# MB_RELAY.net
KiCad netlist of a schematic drawn in Altium Designer
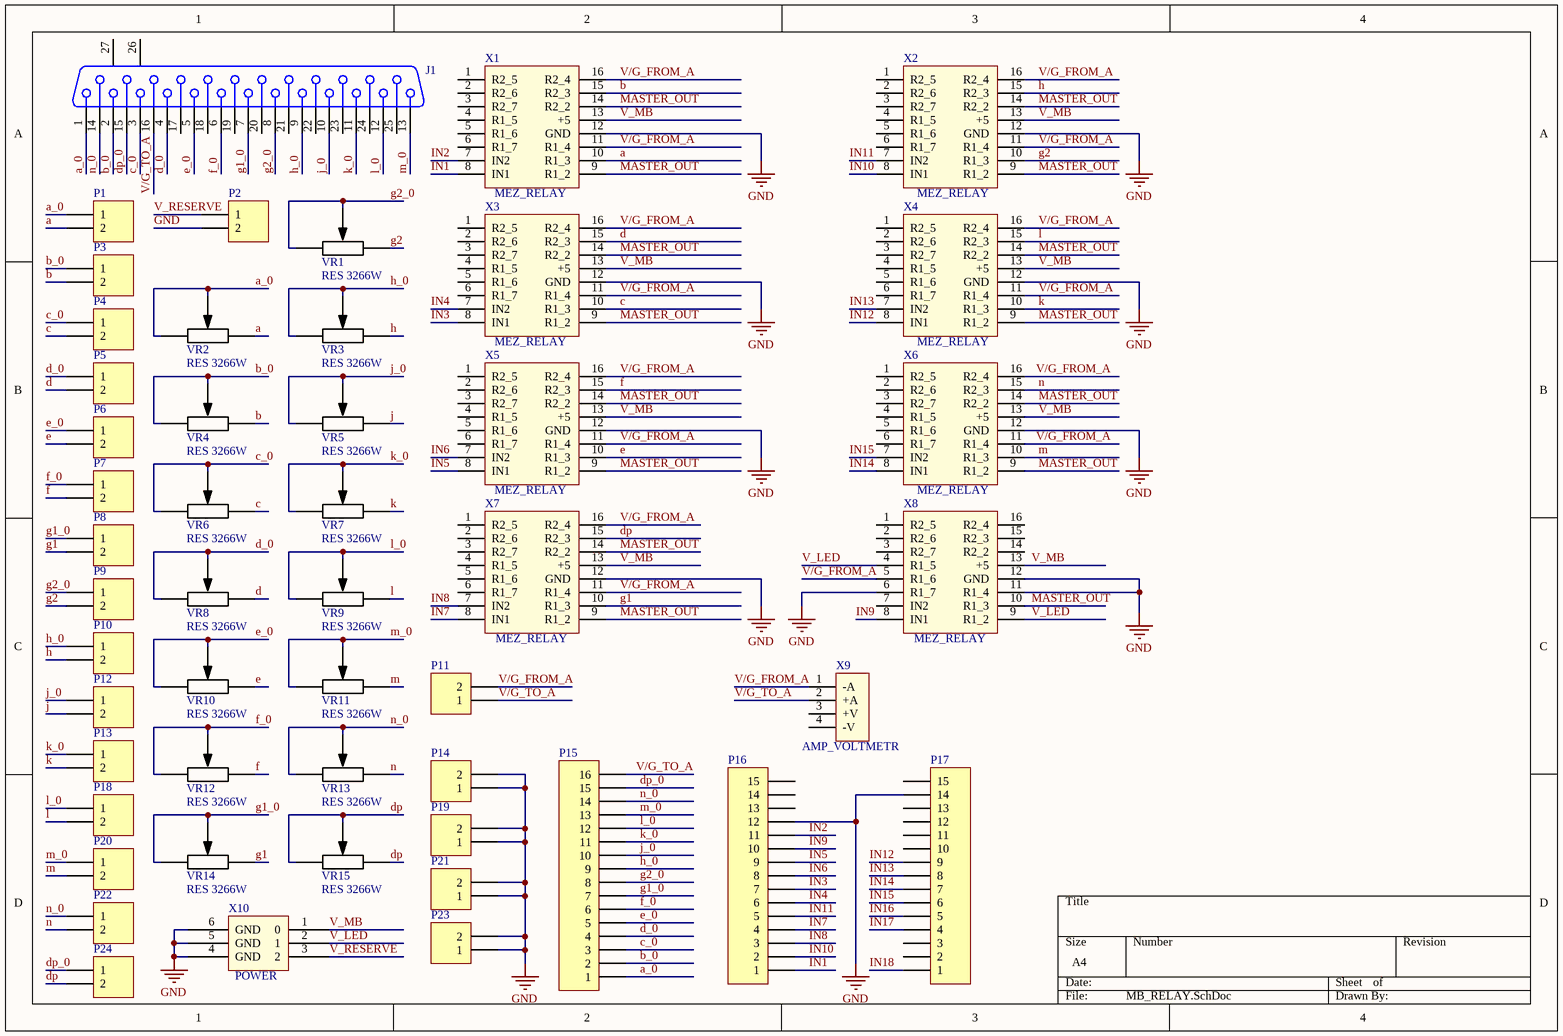
[diagram p0: MB_RELAY.SchDoc]

(export (version "E")
  (design (tool "Eeschema 10.0.6"))
  (components
    (comp (ref "J1")
      (value "D Connector 25")
      (footprint "DSUB1.385-2H25A")
      (description "Receptacle Assembly, 25 Position, Right Angle")
      (fields (field (name "PUBLISHER") "Altium Limited"))
      (libsource (lib "Miscellaneous Connectors") (part "D Connector 25"))
    )
    (comp (ref "P1")
      (value "Header 2")
      (footprint "HDR1X2")
      (description "Header, 2-Pin")
      (fields (field (name "PUBLISHER") "Altium Limited"))
      (libsource (lib "Miscellaneous Connectors") (part "Header 2"))
    )
    (comp (ref "P2")
      (value "Header 2")
      (footprint "HDR1X2")
      (description "Header, 2-Pin")
      (fields (field (name "PUBLISHER") "Altium Limited"))
      (libsource (lib "Miscellaneous Connectors") (part "Header 2"))
    )
    (comp (ref "P3")
      (value "Header 2")
      (footprint "HDR1X2")
      (description "Header, 2-Pin")
      (fields (field (name "PUBLISHER") "Altium Limited"))
      (libsource (lib "Miscellaneous Connectors") (part "Header 2"))
    )
    (comp (ref "P4")
      (value "Header 2")
      (footprint "HDR1X2")
      (description "Header, 2-Pin")
      (fields (field (name "PUBLISHER") "Altium Limited"))
      (libsource (lib "Miscellaneous Connectors") (part "Header 2"))
    )
    (comp (ref "P5")
      (value "Header 2")
      (footprint "HDR1X2")
      (description "Header, 2-Pin")
      (fields (field (name "PUBLISHER") "Altium Limited"))
      (libsource (lib "Miscellaneous Connectors") (part "Header 2"))
    )
    (comp (ref "P6")
      (value "GND")
      (footprint "HDR1X2")
      (description "Header, 2-Pin")
      (fields (field (name "PUBLISHER") "Altium Limited"))
      (libsource (lib "Miscellaneous Connectors") (part "Header 2"))
    )
    (comp (ref "P7")
      (value "GND")
      (footprint "HDR1X2")
      (description "Header, 2-Pin")
      (fields (field (name "PUBLISHER") "Altium Limited"))
      (libsource (lib "Miscellaneous Connectors") (part "Header 2"))
    )
    (comp (ref "P8")
      (value "GND")
      (footprint "HDR1X2")
      (description "Header, 2-Pin")
      (fields (field (name "PUBLISHER") "Altium Limited"))
      (libsource (lib "Miscellaneous Connectors") (part "Header 2"))
    )
    (comp (ref "P9")
      (value "GND")
      (footprint "HDR1X2")
      (description "Header, 2-Pin")
      (fields (field (name "PUBLISHER") "Altium Limited"))
      (libsource (lib "Miscellaneous Connectors") (part "Header 2"))
    )
    (comp (ref "P10")
      (value "Header 2")
      (footprint "HDR1X2")
      (description "Header, 2-Pin")
      (fields (field (name "PUBLISHER") "Altium Limited"))
      (libsource (lib "Miscellaneous Connectors") (part "Header 2"))
    )
    (comp (ref "P11")
      (value "Header 2")
      (footprint "HDR1X2")
      (description "Header, 2-Pin")
      (fields (field (name "PUBLISHER") "Altium Limited"))
      (libsource (lib "") (part "Header 2_1"))
    )
    (comp (ref "P12")
      (value "Header 2")
      (footprint "HDR1X2")
      (description "Header, 2-Pin")
      (fields (field (name "PUBLISHER") "Altium Limited"))
      (libsource (lib "Miscellaneous Connectors") (part "Header 2"))
    )
    (comp (ref "P13")
      (value "GND")
      (footprint "HDR1X2")
      (description "Header, 2-Pin")
      (fields (field (name "PUBLISHER") "Altium Limited"))
      (libsource (lib "Miscellaneous Connectors") (part "Header 2"))
    )
    (comp (ref "P14")
      (value "GND")
      (footprint "HDR1X2")
      (description "Header, 2-Pin")
      (fields (field (name "PUBLISHER") "Altium Limited"))
      (libsource (lib "") (part "Header 2_1"))
    )
    (comp (ref "P15")
      (value "Header 16")
      (footprint "HDR1X16")
      (description "Header, 16-Pin")
      (fields (field (name "PUBLISHER") "Altium Limited"))
      (libsource (lib "Miscellaneous Connectors") (part "Header 16"))
    )
    (comp (ref "P16")
      (value "Header 15")
      (footprint "HDR1X15")
      (description "Header, 15-Pin")
      (fields (field (name "PUBLISHER") "Altium Limited"))
      (libsource (lib "") (part "Header 15_1"))
    )
    (comp (ref "P17")
      (value "Header 15")
      (footprint "HDR1X15")
      (description "Header, 15-Pin")
      (fields (field (name "PUBLISHER") "Altium Limited"))
      (libsource (lib "Miscellaneous Connectors") (part "Header 15"))
    )
    (comp (ref "P18")
      (value "GND")
      (footprint "HDR1X2")
      (description "Header, 2-Pin")
      (fields (field (name "PUBLISHER") "Altium Limited"))
      (libsource (lib "Miscellaneous Connectors") (part "Header 2"))
    )
    (comp (ref "P19")
      (value "GND")
      (footprint "HDR1X2")
      (description "Header, 2-Pin")
      (fields (field (name "PUBLISHER") "Altium Limited"))
      (libsource (lib "") (part "Header 2_1"))
    )
    (comp (ref "P20")
      (value "GND")
      (footprint "HDR1X2")
      (description "Header, 2-Pin")
      (fields (field (name "PUBLISHER") "Altium Limited"))
      (libsource (lib "Miscellaneous Connectors") (part "Header 2"))
    )
    (comp (ref "P21")
      (value "GND")
      (footprint "HDR1X2")
      (description "Header, 2-Pin")
      (fields (field (name "PUBLISHER") "Altium Limited"))
      (libsource (lib "") (part "Header 2_1"))
    )
    (comp (ref "P22")
      (value "GND")
      (footprint "HDR1X2")
      (description "Header, 2-Pin")
      (fields (field (name "PUBLISHER") "Altium Limited"))
      (libsource (lib "Miscellaneous Connectors") (part "Header 2"))
    )
    (comp (ref "P23")
      (value "GND")
      (footprint "HDR1X2")
      (description "Header, 2-Pin")
      (fields (field (name "PUBLISHER") "Altium Limited"))
      (libsource (lib "") (part "Header 2_1"))
    )
    (comp (ref "P24")
      (value "GND")
      (footprint "HDR1X2")
      (description "Header, 2-Pin")
      (fields (field (name "PUBLISHER") "Altium Limited"))
      (libsource (lib "Miscellaneous Connectors") (part "Header 2"))
    )
    (comp (ref "VR1")
      (value "RES 3266W")
      (footprint "aab_Passive:RES 3266W")
      (libsource (lib "aab_Schlib") (part "RES 3266W"))
    )
    (comp (ref "VR2")
      (value "RES 3266W")
      (footprint "aab_Passive:RES 3266W")
      (libsource (lib "aab_Schlib") (part "RES 3266W"))
    )
    (comp (ref "VR3")
      (value "RES 3266W")
      (footprint "aab_Passive:RES 3266W")
      (libsource (lib "aab_Schlib") (part "RES 3266W"))
    )
    (comp (ref "VR4")
      (value "RES 3266W")
      (footprint "aab_Passive:RES 3266W")
      (libsource (lib "aab_Schlib") (part "RES 3266W"))
    )
    (comp (ref "VR5")
      (value "RES 3266W")
      (footprint "aab_Passive:RES 3266W")
      (libsource (lib "aab_Schlib") (part "RES 3266W"))
    )
    (comp (ref "VR6")
      (value "RES 3266W")
      (footprint "aab_Passive:RES 3266W")
      (libsource (lib "aab_Schlib") (part "RES 3266W"))
    )
    (comp (ref "VR7")
      (value "RES 3266W")
      (footprint "aab_Passive:RES 3266W")
      (libsource (lib "aab_Schlib") (part "RES 3266W"))
    )
    (comp (ref "VR8")
      (value "RES 3266W")
      (footprint "aab_Passive:RES 3266W")
      (libsource (lib "aab_Schlib") (part "RES 3266W"))
    )
    (comp (ref "VR9")
      (value "RES 3266W")
      (footprint "aab_Passive:RES 3266W")
      (libsource (lib "aab_Schlib") (part "RES 3266W"))
    )
    (comp (ref "VR10")
      (value "RES 3266W")
      (footprint "aab_Passive:RES 3266W")
      (libsource (lib "aab_Schlib") (part "RES 3266W"))
    )
    (comp (ref "VR11")
      (value "RES 3266W")
      (footprint "aab_Passive:RES 3266W")
      (libsource (lib "aab_Schlib") (part "RES 3266W"))
    )
    (comp (ref "VR12")
      (value "RES 3266W")
      (footprint "aab_Passive:RES 3266W")
      (libsource (lib "aab_Schlib") (part "RES 3266W"))
    )
    (comp (ref "VR13")
      (value "RES 3266W")
      (footprint "aab_Passive:RES 3266W")
      (libsource (lib "aab_Schlib") (part "RES 3266W"))
    )
    (comp (ref "VR14")
      (value "RES 3266W")
      (footprint "aab_Passive:RES 3266W")
      (libsource (lib "aab_Schlib") (part "RES 3266W"))
    )
    (comp (ref "VR15")
      (value "RES 3266W")
      (footprint "aab_Passive:RES 3266W")
      (libsource (lib "aab_Schlib") (part "RES 3266W"))
    )
    (comp (ref "X1")
      (value "MEZ_RELAY")
      (footprint "MEZ_RELAY")
      (libsource (lib "msp_SchLib") (part "MEZ_RELAY"))
    )
    (comp (ref "X2")
      (value "MEZ_RELAY")
      (footprint "MEZ_RELAY")
      (libsource (lib "msp_SchLib") (part "MEZ_RELAY"))
    )
    (comp (ref "X3")
      (value "MEZ_RELAY")
      (footprint "MEZ_RELAY")
      (libsource (lib "msp_SchLib") (part "MEZ_RELAY"))
    )
    (comp (ref "X4")
      (value "MEZ_RELAY")
      (footprint "MEZ_RELAY")
      (libsource (lib "msp_SchLib") (part "MEZ_RELAY"))
    )
    (comp (ref "X5")
      (value "MEZ_RELAY")
      (footprint "MEZ_RELAY")
      (libsource (lib "msp_SchLib") (part "MEZ_RELAY"))
    )
    (comp (ref "X6")
      (value "MEZ_RELAY")
      (footprint "MEZ_RELAY")
      (libsource (lib "msp_SchLib") (part "MEZ_RELAY"))
    )
    (comp (ref "X7")
      (value "MEZ_RELAY")
      (footprint "MEZ_RELAY")
      (libsource (lib "msp_SchLib") (part "MEZ_RELAY"))
    )
    (comp (ref "X8")
      (value "MEZ_RELAY")
      (footprint "MEZ_RELAY")
      (libsource (lib "msp_SchLib") (part "MEZ_RELAY"))
    )
    (comp (ref "X9")
      (value "AMP_VOLTMETR")
      (footprint "vpl_Passive:AMP_VOLTMETER")
      (libsource (lib "msp_SchLib") (part "AMP_VOLTMETR"))
    )
    (comp (ref "X10")
      (value "POWER")
      (footprint "vpl_Passive:POWER")
      (libsource (lib "msp_SchLib") (part "POWER"))
    )
  )
  (nets
    (net (code "1") (name "/IN1") (class "Default")
      (node (ref "P16") (pin "1") (pinfunction "1_1") (pintype "passive"))
      (node (ref "X1") (pin "8") (pinfunction "IN1_8") (pintype "passive"))
    )
    (net (code "2") (name "/IN2") (class "Default")
      (node (ref "P16") (pin "11") (pinfunction "11_11") (pintype "passive"))
      (node (ref "X1") (pin "7") (pinfunction "IN2_7") (pintype "passive"))
    )
    (net (code "3") (name "/IN3") (class "Default")
      (node (ref "P16") (pin "7") (pinfunction "7_7") (pintype "passive"))
      (node (ref "X3") (pin "8") (pinfunction "IN1_8") (pintype "passive"))
    )
    (net (code "4") (name "/IN4") (class "Default")
      (node (ref "P16") (pin "6") (pinfunction "6_6") (pintype "passive"))
      (node (ref "X3") (pin "7") (pinfunction "IN2_7") (pintype "passive"))
    )
    (net (code "5") (name "/IN5") (class "Default")
      (node (ref "P16") (pin "9") (pinfunction "9_9") (pintype "passive"))
      (node (ref "X5") (pin "8") (pinfunction "IN1_8") (pintype "passive"))
    )
    (net (code "6") (name "/IN6") (class "Default")
      (node (ref "P16") (pin "8") (pinfunction "8_8") (pintype "passive"))
      (node (ref "X5") (pin "7") (pinfunction "IN2_7") (pintype "passive"))
    )
    (net (code "7") (name "/IN7") (class "Default")
      (node (ref "P16") (pin "4") (pinfunction "4_4") (pintype "passive"))
      (node (ref "X7") (pin "8") (pinfunction "IN1_8") (pintype "passive"))
    )
    (net (code "8") (name "/IN8") (class "Default")
      (node (ref "P16") (pin "3") (pinfunction "3_3") (pintype "passive"))
      (node (ref "X7") (pin "7") (pinfunction "IN2_7") (pintype "passive"))
    )
    (net (code "9") (name "/IN9") (class "Default")
      (node (ref "P16") (pin "10") (pinfunction "10_10") (pintype "passive"))
      (node (ref "X8") (pin "8") (pinfunction "IN1_8") (pintype "passive"))
    )
    (net (code "10") (name "/IN10") (class "Default")
      (node (ref "P16") (pin "2") (pinfunction "2_2") (pintype "passive"))
      (node (ref "X2") (pin "8") (pinfunction "IN1_8") (pintype "passive"))
    )
    (net (code "11") (name "/IN11") (class "Default")
      (node (ref "P16") (pin "5") (pinfunction "5_5") (pintype "passive"))
      (node (ref "X2") (pin "7") (pinfunction "IN2_7") (pintype "passive"))
    )
    (net (code "12") (name "/IN12") (class "Default")
      (node (ref "P17") (pin "9") (pinfunction "9_9") (pintype "passive"))
      (node (ref "X4") (pin "8") (pinfunction "IN1_8") (pintype "passive"))
    )
    (net (code "13") (name "/IN13") (class "Default")
      (node (ref "P17") (pin "8") (pinfunction "8_8") (pintype "passive"))
      (node (ref "X4") (pin "7") (pinfunction "IN2_7") (pintype "passive"))
    )
    (net (code "14") (name "/IN14") (class "Default")
      (node (ref "P17") (pin "7") (pinfunction "7_7") (pintype "passive"))
      (node (ref "X6") (pin "8") (pinfunction "IN1_8") (pintype "passive"))
    )
    (net (code "15") (name "/IN15") (class "Default")
      (node (ref "P17") (pin "6") (pinfunction "6_6") (pintype "passive"))
      (node (ref "X6") (pin "7") (pinfunction "IN2_7") (pintype "passive"))
    )
    (net (code "16") (name "/IN16") (class "Default")
      (node (ref "P17") (pin "5") (pinfunction "5_5") (pintype "passive"))
    )
    (net (code "17") (name "/IN17") (class "Default")
      (node (ref "P17") (pin "4") (pinfunction "4_4") (pintype "passive"))
    )
    (net (code "18") (name "/IN18") (class "Default")
      (node (ref "P17") (pin "1") (pinfunction "1_1") (pintype "passive"))
    )
    (net (code "19") (name "/MASTER_OUT") (class "Default")
      (node (ref "X1") (pin "14") (pinfunction "R2_2_14") (pintype "passive"))
      (node (ref "X1") (pin "9") (pinfunction "R1_2_9") (pintype "passive"))
      (node (ref "X2") (pin "14") (pinfunction "R2_2_14") (pintype "passive"))
      (node (ref "X2") (pin "9") (pinfunction "R1_2_9") (pintype "passive"))
      (node (ref "X3") (pin "14") (pinfunction "R2_2_14") (pintype "passive"))
      (node (ref "X3") (pin "9") (pinfunction "R1_2_9") (pintype "passive"))
      (node (ref "X4") (pin "14") (pinfunction "R2_2_14") (pintype "passive"))
      (node (ref "X4") (pin "9") (pinfunction "R1_2_9") (pintype "passive"))
      (node (ref "X5") (pin "14") (pinfunction "R2_2_14") (pintype "passive"))
      (node (ref "X5") (pin "9") (pinfunction "R1_2_9") (pintype "passive"))
      (node (ref "X6") (pin "14") (pinfunction "R2_2_14") (pintype "passive"))
      (node (ref "X6") (pin "9") (pinfunction "R1_2_9") (pintype "passive"))
      (node (ref "X7") (pin "14") (pinfunction "R2_2_14") (pintype "passive"))
      (node (ref "X7") (pin "9") (pinfunction "R1_2_9") (pintype "passive"))
      (node (ref "X8") (pin "10") (pinfunction "R1_3_10") (pintype "passive"))
    )
    (net (code "20") (name "/V_LED") (class "Default")
      (node (ref "X10") (pin "2") (pinfunction "1_2") (pintype "passive"))
      (node (ref "X8") (pin "4") (pinfunction "R1_5_4") (pintype "passive"))
      (node (ref "X8") (pin "9") (pinfunction "R1_2_9") (pintype "passive"))
    )
    (net (code "21") (name "/V_MB") (class "Default")
      (node (ref "X1") (pin "13") (pinfunction "+5_13") (pintype "passive"))
      (node (ref "X10") (pin "1") (pinfunction "0_1") (pintype "passive"))
      (node (ref "X2") (pin "13") (pinfunction "+5_13") (pintype "passive"))
      (node (ref "X3") (pin "13") (pinfunction "+5_13") (pintype "passive"))
      (node (ref "X4") (pin "13") (pinfunction "+5_13") (pintype "passive"))
      (node (ref "X5") (pin "13") (pinfunction "+5_13") (pintype "passive"))
      (node (ref "X6") (pin "13") (pinfunction "+5_13") (pintype "passive"))
      (node (ref "X7") (pin "13") (pinfunction "+5_13") (pintype "passive"))
      (node (ref "X8") (pin "13") (pinfunction "+5_13") (pintype "passive"))
    )
    (net (code "22") (name "/V_RESERVE") (class "Default")
      (node (ref "P2") (pin "1") (pinfunction "1_1") (pintype "passive"))
      (node (ref "X10") (pin "3") (pinfunction "2_3") (pintype "passive"))
    )
    (net (code "23") (name "/V{slash}G_FROM_A") (class "Default")
      (node (ref "P11") (pin "2") (pinfunction "2_2") (pintype "passive"))
      (node (ref "X1") (pin "11") (pinfunction "R1_4_11") (pintype "passive"))
      (node (ref "X1") (pin "16") (pinfunction "R2_4_16") (pintype "passive"))
      (node (ref "X2") (pin "11") (pinfunction "R1_4_11") (pintype "passive"))
      (node (ref "X2") (pin "16") (pinfunction "R2_4_16") (pintype "passive"))
      (node (ref "X3") (pin "11") (pinfunction "R1_4_11") (pintype "passive"))
      (node (ref "X3") (pin "16") (pinfunction "R2_4_16") (pintype "passive"))
      (node (ref "X4") (pin "11") (pinfunction "R1_4_11") (pintype "passive"))
      (node (ref "X4") (pin "16") (pinfunction "R2_4_16") (pintype "passive"))
      (node (ref "X5") (pin "11") (pinfunction "R1_4_11") (pintype "passive"))
      (node (ref "X5") (pin "16") (pinfunction "R2_4_16") (pintype "passive"))
      (node (ref "X6") (pin "11") (pinfunction "R1_4_11") (pintype "passive"))
      (node (ref "X6") (pin "16") (pinfunction "R2_4_16") (pintype "passive"))
      (node (ref "X7") (pin "11") (pinfunction "R1_4_11") (pintype "passive"))
      (node (ref "X7") (pin "16") (pinfunction "R2_4_16") (pintype "passive"))
      (node (ref "X8") (pin "5") (pinfunction "R1_6_5") (pintype "passive"))
      (node (ref "X9") (pin "1") (pinfunction "-A_1") (pintype "passive"))
    )
    (net (code "24") (name "/V{slash}G_TO_A") (class "Default")
      (node (ref "J1") (pin "16") (pinfunction "16_16") (pintype "passive"))
      (node (ref "P11") (pin "1") (pinfunction "1_1") (pintype "passive"))
      (node (ref "P15") (pin "16") (pinfunction "16_16") (pintype "passive"))
      (node (ref "X9") (pin "2") (pinfunction "+A_2") (pintype "passive"))
    )
    (net (code "25") (name "/a") (class "Default")
      (node (ref "P1") (pin "2") (pinfunction "2_2") (pintype "passive"))
      (node (ref "VR2") (pin "3") (pinfunction "3_3") (pintype "passive"))
      (node (ref "X1") (pin "10") (pinfunction "R1_3_10") (pintype "passive"))
    )
    (net (code "26") (name "/a_0") (class "Default")
      (node (ref "J1") (pin "1") (pinfunction "1_1") (pintype "passive"))
      (node (ref "P1") (pin "1") (pinfunction "1_1") (pintype "passive"))
      (node (ref "P15") (pin "1") (pinfunction "1_1") (pintype "passive"))
      (node (ref "VR2") (pin "1") (pinfunction "1_1") (pintype "passive"))
      (node (ref "VR2") (pin "2") (pinfunction "2_2") (pintype "passive"))
    )
    (net (code "27") (name "/b") (class "Default")
      (node (ref "P3") (pin "2") (pinfunction "2_2") (pintype "passive"))
      (node (ref "VR4") (pin "3") (pinfunction "3_3") (pintype "passive"))
      (node (ref "X1") (pin "15") (pinfunction "R2_3_15") (pintype "passive"))
    )
    (net (code "28") (name "/b_0") (class "Default")
      (node (ref "J1") (pin "2") (pinfunction "2_2") (pintype "passive"))
      (node (ref "P15") (pin "2") (pinfunction "2_2") (pintype "passive"))
      (node (ref "P3") (pin "1") (pinfunction "1_1") (pintype "passive"))
      (node (ref "VR4") (pin "1") (pinfunction "1_1") (pintype "passive"))
      (node (ref "VR4") (pin "2") (pinfunction "2_2") (pintype "passive"))
    )
    (net (code "29") (name "/c") (class "Default")
      (node (ref "P4") (pin "2") (pinfunction "2_2") (pintype "passive"))
      (node (ref "VR6") (pin "3") (pinfunction "3_3") (pintype "passive"))
      (node (ref "X3") (pin "10") (pinfunction "R1_3_10") (pintype "passive"))
    )
    (net (code "30") (name "/c_0") (class "Default")
      (node (ref "J1") (pin "3") (pinfunction "3_3") (pintype "passive"))
      (node (ref "P15") (pin "3") (pinfunction "3_3") (pintype "passive"))
      (node (ref "P4") (pin "1") (pinfunction "1_1") (pintype "passive"))
      (node (ref "VR6") (pin "1") (pinfunction "1_1") (pintype "passive"))
      (node (ref "VR6") (pin "2") (pinfunction "2_2") (pintype "passive"))
    )
    (net (code "31") (name "/d") (class "Default")
      (node (ref "P5") (pin "2") (pinfunction "2_2") (pintype "passive"))
      (node (ref "VR8") (pin "3") (pinfunction "3_3") (pintype "passive"))
      (node (ref "X3") (pin "15") (pinfunction "R2_3_15") (pintype "passive"))
    )
    (net (code "32") (name "/d_0") (class "Default")
      (node (ref "J1") (pin "4") (pinfunction "4_4") (pintype "passive"))
      (node (ref "P15") (pin "4") (pinfunction "4_4") (pintype "passive"))
      (node (ref "P5") (pin "1") (pinfunction "1_1") (pintype "passive"))
      (node (ref "VR8") (pin "1") (pinfunction "1_1") (pintype "passive"))
      (node (ref "VR8") (pin "2") (pinfunction "2_2") (pintype "passive"))
    )
    (net (code "33") (name "/dp") (class "Default")
      (node (ref "P24") (pin "2") (pinfunction "2_2") (pintype "passive"))
      (node (ref "VR15") (pin "1") (pinfunction "1_1") (pintype "passive"))
      (node (ref "VR15") (pin "2") (pinfunction "2_2") (pintype "passive"))
      (node (ref "VR15") (pin "3") (pinfunction "3_3") (pintype "passive"))
      (node (ref "X7") (pin "15") (pinfunction "R2_3_15") (pintype "passive"))
    )
    (net (code "34") (name "/dp_0") (class "Default")
      (node (ref "J1") (pin "15") (pinfunction "15_15") (pintype "passive"))
      (node (ref "P15") (pin "15") (pinfunction "15_15") (pintype "passive"))
      (node (ref "P24") (pin "1") (pinfunction "1_1") (pintype "passive"))
    )
    (net (code "35") (name "/e") (class "Default")
      (node (ref "P6") (pin "2") (pinfunction "2_2") (pintype "passive"))
      (node (ref "VR10") (pin "3") (pinfunction "3_3") (pintype "passive"))
      (node (ref "X5") (pin "10") (pinfunction "R1_3_10") (pintype "passive"))
    )
    (net (code "36") (name "/e_0") (class "Default")
      (node (ref "J1") (pin "5") (pinfunction "5_5") (pintype "passive"))
      (node (ref "P15") (pin "5") (pinfunction "5_5") (pintype "passive"))
      (node (ref "P6") (pin "1") (pinfunction "1_1") (pintype "passive"))
      (node (ref "VR10") (pin "1") (pinfunction "1_1") (pintype "passive"))
      (node (ref "VR10") (pin "2") (pinfunction "2_2") (pintype "passive"))
    )
    (net (code "37") (name "/f") (class "Default")
      (node (ref "P7") (pin "2") (pinfunction "2_2") (pintype "passive"))
      (node (ref "VR12") (pin "3") (pinfunction "3_3") (pintype "passive"))
      (node (ref "X5") (pin "15") (pinfunction "R2_3_15") (pintype "passive"))
    )
    (net (code "38") (name "/f_0") (class "Default")
      (node (ref "J1") (pin "6") (pinfunction "6_6") (pintype "passive"))
      (node (ref "P15") (pin "6") (pinfunction "6_6") (pintype "passive"))
      (node (ref "P7") (pin "1") (pinfunction "1_1") (pintype "passive"))
      (node (ref "VR12") (pin "1") (pinfunction "1_1") (pintype "passive"))
      (node (ref "VR12") (pin "2") (pinfunction "2_2") (pintype "passive"))
    )
    (net (code "39") (name "/g1") (class "Default")
      (node (ref "P8") (pin "2") (pinfunction "2_2") (pintype "passive"))
      (node (ref "VR14") (pin "3") (pinfunction "3_3") (pintype "passive"))
      (node (ref "X7") (pin "10") (pinfunction "R1_3_10") (pintype "passive"))
    )
    (net (code "40") (name "/g1_0") (class "Default")
      (node (ref "J1") (pin "7") (pinfunction "7_7") (pintype "passive"))
      (node (ref "P15") (pin "7") (pinfunction "7_7") (pintype "passive"))
      (node (ref "P8") (pin "1") (pinfunction "1_1") (pintype "passive"))
      (node (ref "VR14") (pin "1") (pinfunction "1_1") (pintype "passive"))
      (node (ref "VR14") (pin "2") (pinfunction "2_2") (pintype "passive"))
    )
    (net (code "41") (name "/g2") (class "Default")
      (node (ref "P9") (pin "2") (pinfunction "2_2") (pintype "passive"))
      (node (ref "VR1") (pin "3") (pinfunction "3_3") (pintype "passive"))
      (node (ref "X2") (pin "10") (pinfunction "R1_3_10") (pintype "passive"))
    )
    (net (code "42") (name "/g2_0") (class "Default")
      (node (ref "J1") (pin "8") (pinfunction "8_8") (pintype "passive"))
      (node (ref "P15") (pin "8") (pinfunction "8_8") (pintype "passive"))
      (node (ref "P9") (pin "1") (pinfunction "1_1") (pintype "passive"))
      (node (ref "VR1") (pin "1") (pinfunction "1_1") (pintype "passive"))
      (node (ref "VR1") (pin "2") (pinfunction "2_2") (pintype "passive"))
    )
    (net (code "43") (name "/h") (class "Default")
      (node (ref "P10") (pin "2") (pinfunction "2_2") (pintype "passive"))
      (node (ref "VR3") (pin "3") (pinfunction "3_3") (pintype "passive"))
      (node (ref "X2") (pin "15") (pinfunction "R2_3_15") (pintype "passive"))
    )
    (net (code "44") (name "/h_0") (class "Default")
      (node (ref "J1") (pin "9") (pinfunction "9_9") (pintype "passive"))
      (node (ref "P10") (pin "1") (pinfunction "1_1") (pintype "passive"))
      (node (ref "P15") (pin "9") (pinfunction "9_9") (pintype "passive"))
      (node (ref "VR3") (pin "1") (pinfunction "1_1") (pintype "passive"))
      (node (ref "VR3") (pin "2") (pinfunction "2_2") (pintype "passive"))
    )
    (net (code "45") (name "/j") (class "Default")
      (node (ref "P12") (pin "2") (pinfunction "2_2") (pintype "passive"))
      (node (ref "VR5") (pin "3") (pinfunction "3_3") (pintype "passive"))
    )
    (net (code "46") (name "/j_0") (class "Default")
      (node (ref "J1") (pin "10") (pinfunction "10_10") (pintype "passive"))
      (node (ref "P12") (pin "1") (pinfunction "1_1") (pintype "passive"))
      (node (ref "P15") (pin "10") (pinfunction "10_10") (pintype "passive"))
      (node (ref "VR5") (pin "1") (pinfunction "1_1") (pintype "passive"))
      (node (ref "VR5") (pin "2") (pinfunction "2_2") (pintype "passive"))
    )
    (net (code "47") (name "/k") (class "Default")
      (node (ref "P13") (pin "2") (pinfunction "2_2") (pintype "passive"))
      (node (ref "VR7") (pin "3") (pinfunction "3_3") (pintype "passive"))
      (node (ref "X4") (pin "10") (pinfunction "R1_3_10") (pintype "passive"))
    )
    (net (code "48") (name "/k_0") (class "Default")
      (node (ref "J1") (pin "11") (pinfunction "11_11") (pintype "passive"))
      (node (ref "P13") (pin "1") (pinfunction "1_1") (pintype "passive"))
      (node (ref "P15") (pin "11") (pinfunction "11_11") (pintype "passive"))
      (node (ref "VR7") (pin "1") (pinfunction "1_1") (pintype "passive"))
      (node (ref "VR7") (pin "2") (pinfunction "2_2") (pintype "passive"))
    )
    (net (code "49") (name "/l") (class "Default")
      (node (ref "P18") (pin "2") (pinfunction "2_2") (pintype "passive"))
      (node (ref "VR9") (pin "3") (pinfunction "3_3") (pintype "passive"))
      (node (ref "X4") (pin "15") (pinfunction "R2_3_15") (pintype "passive"))
    )
    (net (code "50") (name "/l_0") (class "Default")
      (node (ref "J1") (pin "12") (pinfunction "12_12") (pintype "passive"))
      (node (ref "P15") (pin "12") (pinfunction "12_12") (pintype "passive"))
      (node (ref "P18") (pin "1") (pinfunction "1_1") (pintype "passive"))
      (node (ref "VR9") (pin "1") (pinfunction "1_1") (pintype "passive"))
      (node (ref "VR9") (pin "2") (pinfunction "2_2") (pintype "passive"))
    )
    (net (code "51") (name "/m") (class "Default")
      (node (ref "P20") (pin "2") (pinfunction "2_2") (pintype "passive"))
      (node (ref "VR11") (pin "3") (pinfunction "3_3") (pintype "passive"))
      (node (ref "X6") (pin "10") (pinfunction "R1_3_10") (pintype "passive"))
    )
    (net (code "52") (name "/m_0") (class "Default")
      (node (ref "J1") (pin "13") (pinfunction "13_13") (pintype "passive"))
      (node (ref "P15") (pin "13") (pinfunction "13_13") (pintype "passive"))
      (node (ref "P20") (pin "1") (pinfunction "1_1") (pintype "passive"))
      (node (ref "VR11") (pin "1") (pinfunction "1_1") (pintype "passive"))
      (node (ref "VR11") (pin "2") (pinfunction "2_2") (pintype "passive"))
    )
    (net (code "53") (name "/n") (class "Default")
      (node (ref "P22") (pin "2") (pinfunction "2_2") (pintype "passive"))
      (node (ref "VR13") (pin "3") (pinfunction "3_3") (pintype "passive"))
      (node (ref "X6") (pin "15") (pinfunction "R2_3_15") (pintype "passive"))
    )
    (net (code "54") (name "/n_0") (class "Default")
      (node (ref "J1") (pin "14") (pinfunction "14_14") (pintype "passive"))
      (node (ref "P15") (pin "14") (pinfunction "14_14") (pintype "passive"))
      (node (ref "P22") (pin "1") (pinfunction "1_1") (pintype "passive"))
      (node (ref "VR13") (pin "1") (pinfunction "1_1") (pintype "passive"))
      (node (ref "VR13") (pin "2") (pinfunction "2_2") (pintype "passive"))
    )
    (net (code "55") (name "GND") (class "Default")
      (node (ref "P14") (pin "1") (pinfunction "1_1") (pintype "passive"))
      (node (ref "P14") (pin "2") (pinfunction "2_2") (pintype "passive"))
      (node (ref "P16") (pin "12") (pinfunction "12_12") (pintype "passive"))
      (node (ref "P17") (pin "14") (pinfunction "14_14") (pintype "passive"))
      (node (ref "P19") (pin "1") (pinfunction "1_1") (pintype "passive"))
      (node (ref "P19") (pin "2") (pinfunction "2_2") (pintype "passive"))
      (node (ref "P2") (pin "2") (pinfunction "2_2") (pintype "passive"))
      (node (ref "P21") (pin "1") (pinfunction "1_1") (pintype "passive"))
      (node (ref "P21") (pin "2") (pinfunction "2_2") (pintype "passive"))
      (node (ref "P23") (pin "1") (pinfunction "1_1") (pintype "passive"))
      (node (ref "P23") (pin "2") (pinfunction "2_2") (pintype "passive"))
      (node (ref "X1") (pin "12") (pinfunction "GND_12") (pintype "passive"))
      (node (ref "X10") (pin "4") (pinfunction "GND_4") (pintype "passive"))
      (node (ref "X10") (pin "5") (pinfunction "GND_5") (pintype "passive"))
      (node (ref "X10") (pin "6") (pinfunction "GND_6") (pintype "passive"))
      (node (ref "X2") (pin "12") (pinfunction "GND_12") (pintype "passive"))
      (node (ref "X3") (pin "12") (pinfunction "GND_12") (pintype "passive"))
      (node (ref "X4") (pin "12") (pinfunction "GND_12") (pintype "passive"))
      (node (ref "X5") (pin "12") (pinfunction "GND_12") (pintype "passive"))
      (node (ref "X6") (pin "12") (pinfunction "GND_12") (pintype "passive"))
      (node (ref "X7") (pin "12") (pinfunction "GND_12") (pintype "passive"))
      (node (ref "X8") (pin "11") (pinfunction "R1_4_11") (pintype "passive"))
      (node (ref "X8") (pin "12") (pinfunction "GND_12") (pintype "passive"))
      (node (ref "X8") (pin "6") (pinfunction "R1_7_6") (pintype "passive"))
    )
    (net (code "56") (name "unconnected-(J1-MH1-Pad26)") (class "Default")
      (node (ref "J1") (pin "26") (pinfunction "MH1_26") (pintype "passive"))
    )
    (net (code "57") (name "unconnected-(J1-MH2-Pad27)") (class "Default")
      (node (ref "J1") (pin "27") (pinfunction "MH2_27") (pintype "passive"))
    )
    (net (code "58") (name "unconnected-(J1-Pad17)") (class "Default")
      (node (ref "J1") (pin "17") (pinfunction "17_17") (pintype "passive"))
    )
    (net (code "59") (name "unconnected-(J1-Pad18)") (class "Default")
      (node (ref "J1") (pin "18") (pinfunction "18_18") (pintype "passive"))
    )
    (net (code "60") (name "unconnected-(J1-Pad19)") (class "Default")
      (node (ref "J1") (pin "19") (pinfunction "19_19") (pintype "passive"))
    )
    (net (code "61") (name "unconnected-(J1-Pad20)") (class "Default")
      (node (ref "J1") (pin "20") (pinfunction "20_20") (pintype "passive"))
    )
    (net (code "62") (name "unconnected-(J1-Pad21)") (class "Default")
      (node (ref "J1") (pin "21") (pinfunction "21_21") (pintype "passive"))
    )
    (net (code "63") (name "unconnected-(J1-Pad22)") (class "Default")
      (node (ref "J1") (pin "22") (pinfunction "22_22") (pintype "passive"))
    )
    (net (code "64") (name "unconnected-(J1-Pad23)") (class "Default")
      (node (ref "J1") (pin "23") (pinfunction "23_23") (pintype "passive"))
    )
    (net (code "65") (name "unconnected-(J1-Pad24)") (class "Default")
      (node (ref "J1") (pin "24") (pinfunction "24_24") (pintype "passive"))
    )
    (net (code "66") (name "unconnected-(J1-Pad25)") (class "Default")
      (node (ref "J1") (pin "25") (pinfunction "25_25") (pintype "passive"))
    )
    (net (code "67") (name "unconnected-(P16-Pad13)") (class "Default")
      (node (ref "P16") (pin "13") (pinfunction "13_13") (pintype "passive"))
    )
    (net (code "68") (name "unconnected-(P16-Pad14)") (class "Default")
      (node (ref "P16") (pin "14") (pinfunction "14_14") (pintype "passive"))
    )
    (net (code "69") (name "unconnected-(P16-Pad15)") (class "Default")
      (node (ref "P16") (pin "15") (pinfunction "15_15") (pintype "passive"))
    )
    (net (code "70") (name "unconnected-(P17-Pad2)") (class "Default")
      (node (ref "P17") (pin "2") (pinfunction "2_2") (pintype "passive"))
    )
    (net (code "71") (name "unconnected-(P17-Pad3)") (class "Default")
      (node (ref "P17") (pin "3") (pinfunction "3_3") (pintype "passive"))
    )
    (net (code "72") (name "unconnected-(P17-Pad10)") (class "Default")
      (node (ref "P17") (pin "10") (pinfunction "10_10") (pintype "passive"))
    )
    (net (code "73") (name "unconnected-(P17-Pad11)") (class "Default")
      (node (ref "P17") (pin "11") (pinfunction "11_11") (pintype "passive"))
    )
    (net (code "74") (name "unconnected-(P17-Pad12)") (class "Default")
      (node (ref "P17") (pin "12") (pinfunction "12_12") (pintype "passive"))
    )
    (net (code "75") (name "unconnected-(P17-Pad13)") (class "Default")
      (node (ref "P17") (pin "13") (pinfunction "13_13") (pintype "passive"))
    )
    (net (code "76") (name "unconnected-(P17-Pad15)") (class "Default")
      (node (ref "P17") (pin "15") (pinfunction "15_15") (pintype "passive"))
    )
    (net (code "77") (name "unconnected-(X1-R1_5-Pad4)") (class "Default")
      (node (ref "X1") (pin "4") (pinfunction "R1_5_4") (pintype "passive"))
    )
    (net (code "78") (name "unconnected-(X1-R1_6-Pad5)") (class "Default")
      (node (ref "X1") (pin "5") (pinfunction "R1_6_5") (pintype "passive"))
    )
    (net (code "79") (name "unconnected-(X1-R1_7-Pad6)") (class "Default")
      (node (ref "X1") (pin "6") (pinfunction "R1_7_6") (pintype "passive"))
    )
    (net (code "80") (name "unconnected-(X1-R2_5-Pad1)") (class "Default")
      (node (ref "X1") (pin "1") (pinfunction "R2_5_1") (pintype "passive"))
    )
    (net (code "81") (name "unconnected-(X1-R2_6-Pad2)") (class "Default")
      (node (ref "X1") (pin "2") (pinfunction "R2_6_2") (pintype "passive"))
    )
    (net (code "82") (name "unconnected-(X1-R2_7-Pad3)") (class "Default")
      (node (ref "X1") (pin "3") (pinfunction "R2_7_3") (pintype "passive"))
    )
    (net (code "83") (name "unconnected-(X2-R1_5-Pad4)") (class "Default")
      (node (ref "X2") (pin "4") (pinfunction "R1_5_4") (pintype "passive"))
    )
    (net (code "84") (name "unconnected-(X2-R1_6-Pad5)") (class "Default")
      (node (ref "X2") (pin "5") (pinfunction "R1_6_5") (pintype "passive"))
    )
    (net (code "85") (name "unconnected-(X2-R1_7-Pad6)") (class "Default")
      (node (ref "X2") (pin "6") (pinfunction "R1_7_6") (pintype "passive"))
    )
    (net (code "86") (name "unconnected-(X2-R2_5-Pad1)") (class "Default")
      (node (ref "X2") (pin "1") (pinfunction "R2_5_1") (pintype "passive"))
    )
    (net (code "87") (name "unconnected-(X2-R2_6-Pad2)") (class "Default")
      (node (ref "X2") (pin "2") (pinfunction "R2_6_2") (pintype "passive"))
    )
    (net (code "88") (name "unconnected-(X2-R2_7-Pad3)") (class "Default")
      (node (ref "X2") (pin "3") (pinfunction "R2_7_3") (pintype "passive"))
    )
    (net (code "89") (name "unconnected-(X3-R1_5-Pad4)") (class "Default")
      (node (ref "X3") (pin "4") (pinfunction "R1_5_4") (pintype "passive"))
    )
    (net (code "90") (name "unconnected-(X3-R1_6-Pad5)") (class "Default")
      (node (ref "X3") (pin "5") (pinfunction "R1_6_5") (pintype "passive"))
    )
    (net (code "91") (name "unconnected-(X3-R1_7-Pad6)") (class "Default")
      (node (ref "X3") (pin "6") (pinfunction "R1_7_6") (pintype "passive"))
    )
    (net (code "92") (name "unconnected-(X3-R2_5-Pad1)") (class "Default")
      (node (ref "X3") (pin "1") (pinfunction "R2_5_1") (pintype "passive"))
    )
    (net (code "93") (name "unconnected-(X3-R2_6-Pad2)") (class "Default")
      (node (ref "X3") (pin "2") (pinfunction "R2_6_2") (pintype "passive"))
    )
    (net (code "94") (name "unconnected-(X3-R2_7-Pad3)") (class "Default")
      (node (ref "X3") (pin "3") (pinfunction "R2_7_3") (pintype "passive"))
    )
    (net (code "95") (name "unconnected-(X4-R1_5-Pad4)") (class "Default")
      (node (ref "X4") (pin "4") (pinfunction "R1_5_4") (pintype "passive"))
    )
    (net (code "96") (name "unconnected-(X4-R1_6-Pad5)") (class "Default")
      (node (ref "X4") (pin "5") (pinfunction "R1_6_5") (pintype "passive"))
    )
    (net (code "97") (name "unconnected-(X4-R1_7-Pad6)") (class "Default")
      (node (ref "X4") (pin "6") (pinfunction "R1_7_6") (pintype "passive"))
    )
    (net (code "98") (name "unconnected-(X4-R2_5-Pad1)") (class "Default")
      (node (ref "X4") (pin "1") (pinfunction "R2_5_1") (pintype "passive"))
    )
    (net (code "99") (name "unconnected-(X4-R2_6-Pad2)") (class "Default")
      (node (ref "X4") (pin "2") (pinfunction "R2_6_2") (pintype "passive"))
    )
    (net (code "100") (name "unconnected-(X4-R2_7-Pad3)") (class "Default")
      (node (ref "X4") (pin "3") (pinfunction "R2_7_3") (pintype "passive"))
    )
    (net (code "101") (name "unconnected-(X5-R1_5-Pad4)") (class "Default")
      (node (ref "X5") (pin "4") (pinfunction "R1_5_4") (pintype "passive"))
    )
    (net (code "102") (name "unconnected-(X5-R1_6-Pad5)") (class "Default")
      (node (ref "X5") (pin "5") (pinfunction "R1_6_5") (pintype "passive"))
    )
    (net (code "103") (name "unconnected-(X5-R1_7-Pad6)") (class "Default")
      (node (ref "X5") (pin "6") (pinfunction "R1_7_6") (pintype "passive"))
    )
    (net (code "104") (name "unconnected-(X5-R2_5-Pad1)") (class "Default")
      (node (ref "X5") (pin "1") (pinfunction "R2_5_1") (pintype "passive"))
    )
    (net (code "105") (name "unconnected-(X5-R2_6-Pad2)") (class "Default")
      (node (ref "X5") (pin "2") (pinfunction "R2_6_2") (pintype "passive"))
    )
    (net (code "106") (name "unconnected-(X5-R2_7-Pad3)") (class "Default")
      (node (ref "X5") (pin "3") (pinfunction "R2_7_3") (pintype "passive"))
    )
    (net (code "107") (name "unconnected-(X6-R1_5-Pad4)") (class "Default")
      (node (ref "X6") (pin "4") (pinfunction "R1_5_4") (pintype "passive"))
    )
    (net (code "108") (name "unconnected-(X6-R1_6-Pad5)") (class "Default")
      (node (ref "X6") (pin "5") (pinfunction "R1_6_5") (pintype "passive"))
    )
    (net (code "109") (name "unconnected-(X6-R1_7-Pad6)") (class "Default")
      (node (ref "X6") (pin "6") (pinfunction "R1_7_6") (pintype "passive"))
    )
    (net (code "110") (name "unconnected-(X6-R2_5-Pad1)") (class "Default")
      (node (ref "X6") (pin "1") (pinfunction "R2_5_1") (pintype "passive"))
    )
    (net (code "111") (name "unconnected-(X6-R2_6-Pad2)") (class "Default")
      (node (ref "X6") (pin "2") (pinfunction "R2_6_2") (pintype "passive"))
    )
    (net (code "112") (name "unconnected-(X6-R2_7-Pad3)") (class "Default")
      (node (ref "X6") (pin "3") (pinfunction "R2_7_3") (pintype "passive"))
    )
    (net (code "113") (name "unconnected-(X7-R1_5-Pad4)") (class "Default")
      (node (ref "X7") (pin "4") (pinfunction "R1_5_4") (pintype "passive"))
    )
    (net (code "114") (name "unconnected-(X7-R1_6-Pad5)") (class "Default")
      (node (ref "X7") (pin "5") (pinfunction "R1_6_5") (pintype "passive"))
    )
    (net (code "115") (name "unconnected-(X7-R1_7-Pad6)") (class "Default")
      (node (ref "X7") (pin "6") (pinfunction "R1_7_6") (pintype "passive"))
    )
    (net (code "116") (name "unconnected-(X7-R2_5-Pad1)") (class "Default")
      (node (ref "X7") (pin "1") (pinfunction "R2_5_1") (pintype "passive"))
    )
    (net (code "117") (name "unconnected-(X7-R2_6-Pad2)") (class "Default")
      (node (ref "X7") (pin "2") (pinfunction "R2_6_2") (pintype "passive"))
    )
    (net (code "118") (name "unconnected-(X7-R2_7-Pad3)") (class "Default")
      (node (ref "X7") (pin "3") (pinfunction "R2_7_3") (pintype "passive"))
    )
    (net (code "119") (name "unconnected-(X8-IN2-Pad7)") (class "Default")
      (node (ref "X8") (pin "7") (pinfunction "IN2_7") (pintype "passive"))
    )
    (net (code "120") (name "unconnected-(X8-R2_2-Pad14)") (class "Default")
      (node (ref "X8") (pin "14") (pinfunction "R2_2_14") (pintype "passive"))
    )
    (net (code "121") (name "unconnected-(X8-R2_3-Pad15)") (class "Default")
      (node (ref "X8") (pin "15") (pinfunction "R2_3_15") (pintype "passive"))
    )
    (net (code "122") (name "unconnected-(X8-R2_4-Pad16)") (class "Default")
      (node (ref "X8") (pin "16") (pinfunction "R2_4_16") (pintype "passive"))
    )
    (net (code "123") (name "unconnected-(X8-R2_5-Pad1)") (class "Default")
      (node (ref "X8") (pin "1") (pinfunction "R2_5_1") (pintype "passive"))
    )
    (net (code "124") (name "unconnected-(X8-R2_6-Pad2)") (class "Default")
      (node (ref "X8") (pin "2") (pinfunction "R2_6_2") (pintype "passive"))
    )
    (net (code "125") (name "unconnected-(X8-R2_7-Pad3)") (class "Default")
      (node (ref "X8") (pin "3") (pinfunction "R2_7_3") (pintype "passive"))
    )
    (net (code "126") (name "unconnected-(X9-+V-Pad3)") (class "Default")
      (node (ref "X9") (pin "3") (pinfunction "+V_3") (pintype "passive"))
    )
    (net (code "127") (name "unconnected-(X9--V-Pad4)") (class "Default")
      (node (ref "X9") (pin "4") (pinfunction "-V_4") (pintype "passive"))
    )
  )
)
